# emu.net
KiCad netlist of a schematic drawn in EAGLE
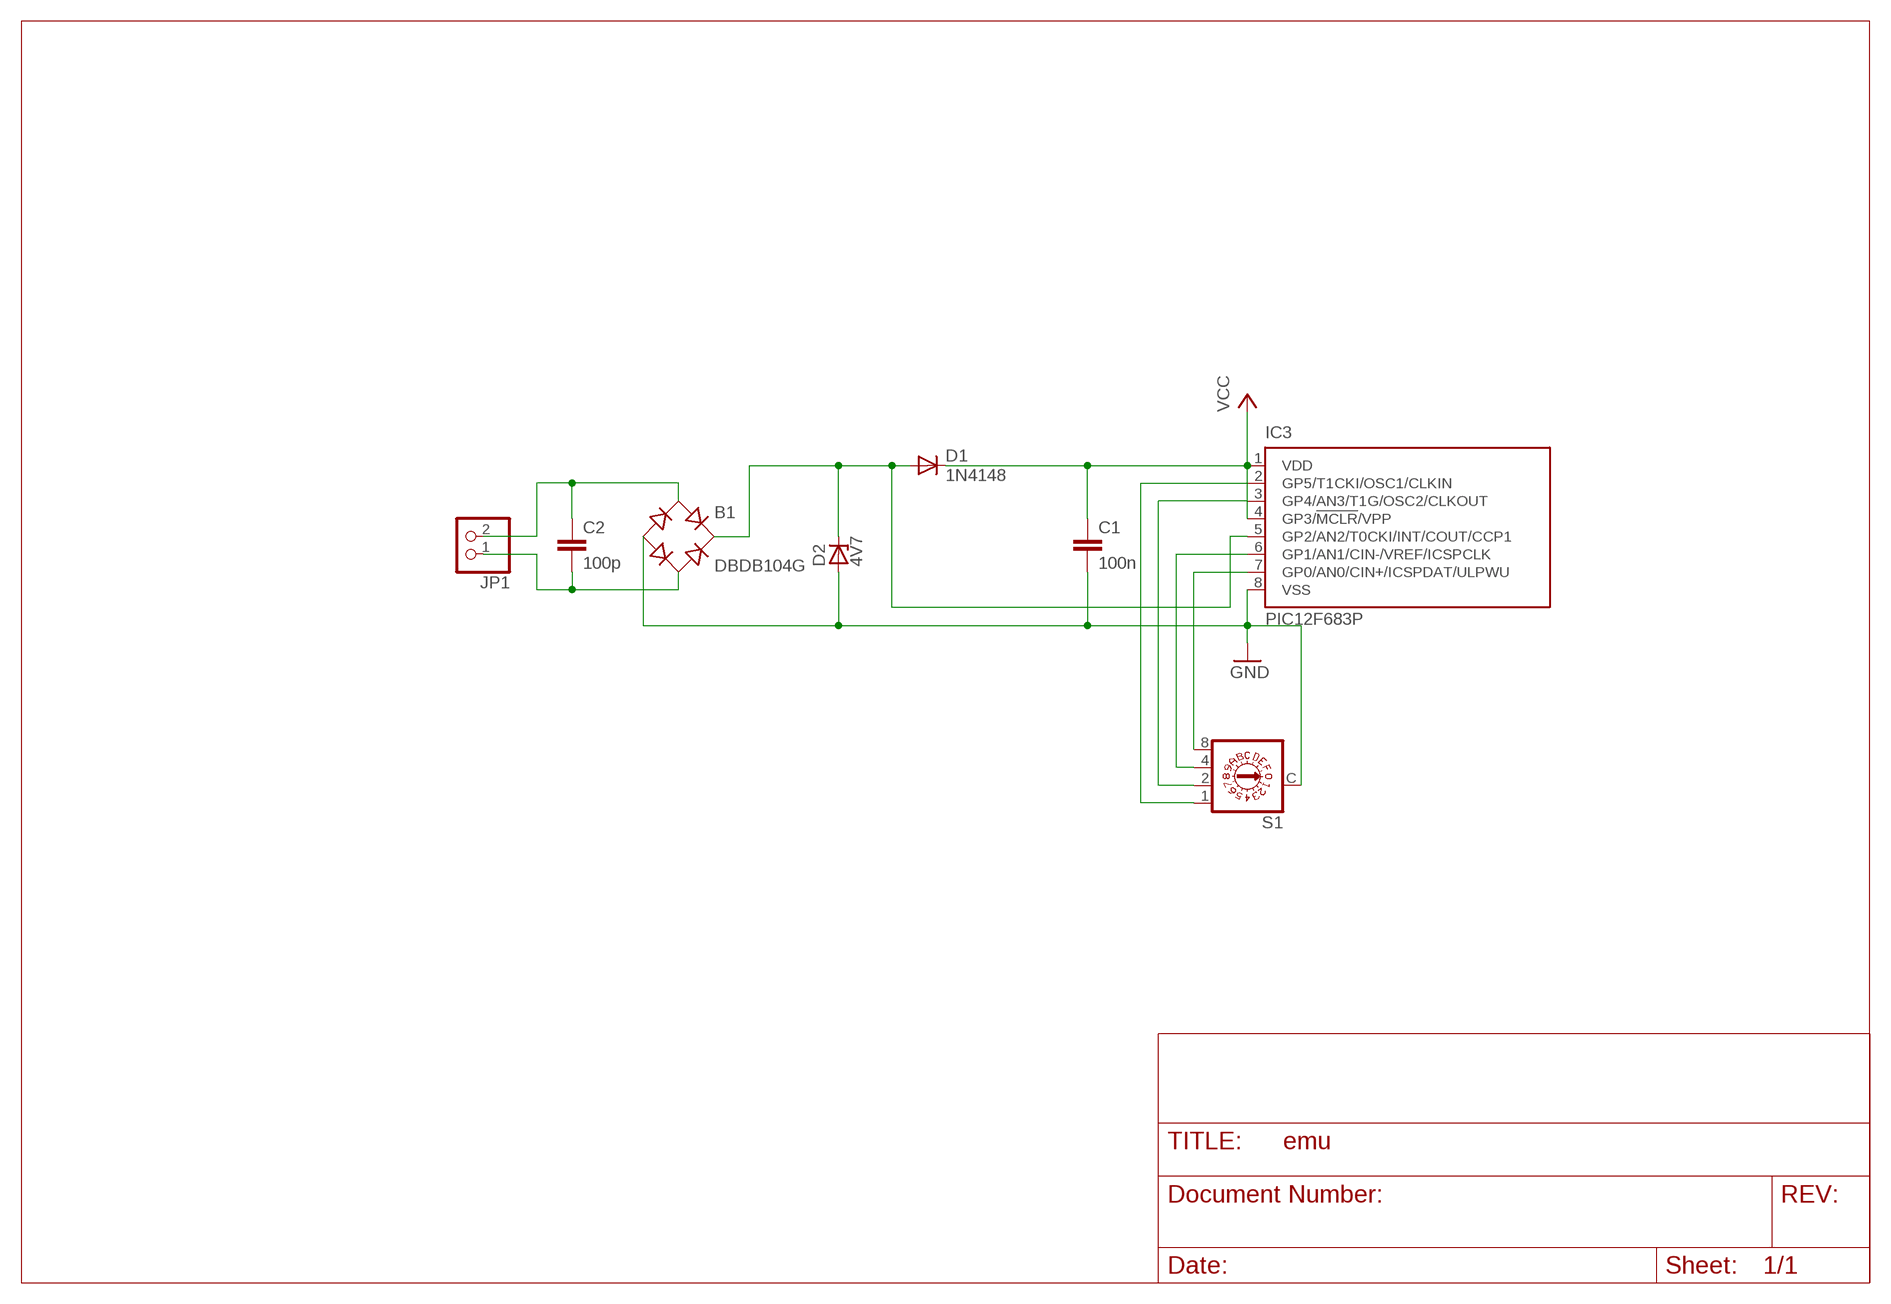
[diagram p0: schematic, sheet 1]

(export (version "E")
  (design (tool "Eeschema 10.0.6"))
  (components
    (comp (ref "B1")
      (value "DBDB104G")
      (footprint "eagle-import:DB")
      (libsource (lib "eagle-import") (part "DB?GDB104"))
    )
    (comp (ref "C1")
      (value "100n")
      (footprint "eagle-import:C025-025X050")
      (libsource (lib "eagle-import") (part "C-EU025-025X050"))
    )
    (comp (ref "C2")
      (value "100p")
      (footprint "eagle-import:C025-025X050")
      (libsource (lib "eagle-import") (part "C-EU025-025X050"))
    )
    (comp (ref "D1")
      (value "1N4148")
      (footprint "eagle-import:DO35-7")
      (libsource (lib "eagle-import") (part "1N4148DO35-7"))
    )
    (comp (ref "D2")
      (value "4V7")
      (footprint "eagle-import:ZDIO-5")
      (libsource (lib "eagle-import") (part "ZENER-DIODEZD-5"))
    )
    (comp (ref "IC3")
      (value "PIC12F683P")
      (footprint "eagle-import:DIL8")
      (fields (field (name "MF") "MICROCHIP") (field (name "MPN") "PIC12F683-I/P"))
      (libsource (lib "eagle-import") (part "PIC12F683P"))
    )
    (comp (ref "JP1")
      (value "PINHD-1X2/90")
      (footprint "eagle-import:1X02_90")
      (libsource (lib "eagle-import") (part "PINHD-1X2/90"))
    )
    (comp (ref "S1")
      (value "S10HEX")
      (footprint "eagle-import:S10HEX")
      (libsource (lib "eagle-import") (part "S10HEX"))
    )
  )
  (nets
    (net (code "1") (name "GND") (class "Default")
      (node (ref "B1") (pin "-") (pinfunction "-_-") (pintype "passive"))
      (node (ref "C1") (pin "2") (pinfunction "2_2") (pintype "passive"))
      (node (ref "D2") (pin "A") (pinfunction "A_A") (pintype "passive"))
      (node (ref "IC3") (pin "8") (pinfunction "VSS_8") (pintype "power_in"))
      (node (ref "S1") (pin "C") (pinfunction "C_C") (pintype "passive"))
    )
    (net (code "2") (name "Net-(B1-PadAC1)") (class "Default")
      (node (ref "B1") (pin "AC1") (pinfunction "AC1_AC1") (pintype "passive"))
      (node (ref "C2") (pin "1") (pinfunction "1_1") (pintype "passive"))
      (node (ref "JP1") (pin "2") (pinfunction "2_2") (pintype "passive"))
    )
    (net (code "3") (name "Net-(B1-PadAC2)") (class "Default")
      (node (ref "B1") (pin "AC2") (pinfunction "AC2_AC2") (pintype "passive"))
      (node (ref "C2") (pin "2") (pinfunction "2_2") (pintype "passive"))
      (node (ref "JP1") (pin "1") (pinfunction "1_1") (pintype "passive"))
    )
    (net (code "4") (name "Net-(IC3-GP0{slash}AN0{slash}CIN+{slash}ICSPDAT{slash}ULPWU)") (class "Default")
      (node (ref "IC3") (pin "7") (pinfunction "GP0/AN0/CIN+/ICSPDAT/ULPWU_7") (pintype "bidirectional"))
      (node (ref "S1") (pin "8") (pinfunction "8_8") (pintype "passive"))
    )
    (net (code "5") (name "Net-(IC3-GP1{slash}AN1{slash}CIN-{slash}VREF{slash}ICSPCLK)") (class "Default")
      (node (ref "IC3") (pin "6") (pinfunction "GP1/AN1/CIN-/VREF/ICSPCLK_6") (pintype "bidirectional"))
      (node (ref "S1") (pin "4") (pinfunction "4_4") (pintype "passive"))
    )
    (net (code "6") (name "Net-(IC3-GP2{slash}AN2{slash}T0CKI{slash}INT{slash}COUT{slash}CCP1)") (class "Default")
      (node (ref "B1") (pin "+") (pinfunction "+_+") (pintype "passive"))
      (node (ref "D1") (pin "A") (pinfunction "A_A") (pintype "passive"))
      (node (ref "D2") (pin "C") (pinfunction "C_C") (pintype "passive"))
      (node (ref "IC3") (pin "5") (pinfunction "GP2/AN2/T0CKI/INT/COUT/CCP1_5") (pintype "bidirectional"))
    )
    (net (code "7") (name "Net-(IC3-GP4{slash}AN3{slash}T1G{slash}OSC2{slash}CLKOUT)") (class "Default")
      (node (ref "IC3") (pin "3") (pinfunction "GP4/AN3/T1G/OSC2/CLKOUT_3") (pintype "bidirectional"))
      (node (ref "S1") (pin "2") (pinfunction "2_2") (pintype "passive"))
    )
    (net (code "8") (name "Net-(IC3-GP5{slash}T1CKI{slash}OSC1{slash}CLKIN)") (class "Default")
      (node (ref "IC3") (pin "2") (pinfunction "GP5/T1CKI/OSC1/CLKIN_2") (pintype "bidirectional"))
      (node (ref "S1") (pin "1") (pinfunction "1_1") (pintype "passive"))
    )
    (net (code "9") (name "VCC") (class "Default")
      (node (ref "C1") (pin "1") (pinfunction "1_1") (pintype "passive"))
      (node (ref "D1") (pin "C") (pinfunction "C_C") (pintype "passive"))
      (node (ref "IC3") (pin "1") (pinfunction "VDD_1") (pintype "power_in"))
      (node (ref "IC3") (pin "4") (pinfunction "GP3/~{MCLR}/VPP_4") (pintype "bidirectional"))
    )
  )
)
